# MCU.net
KiCad netlist of a schematic drawn in Altium Designer
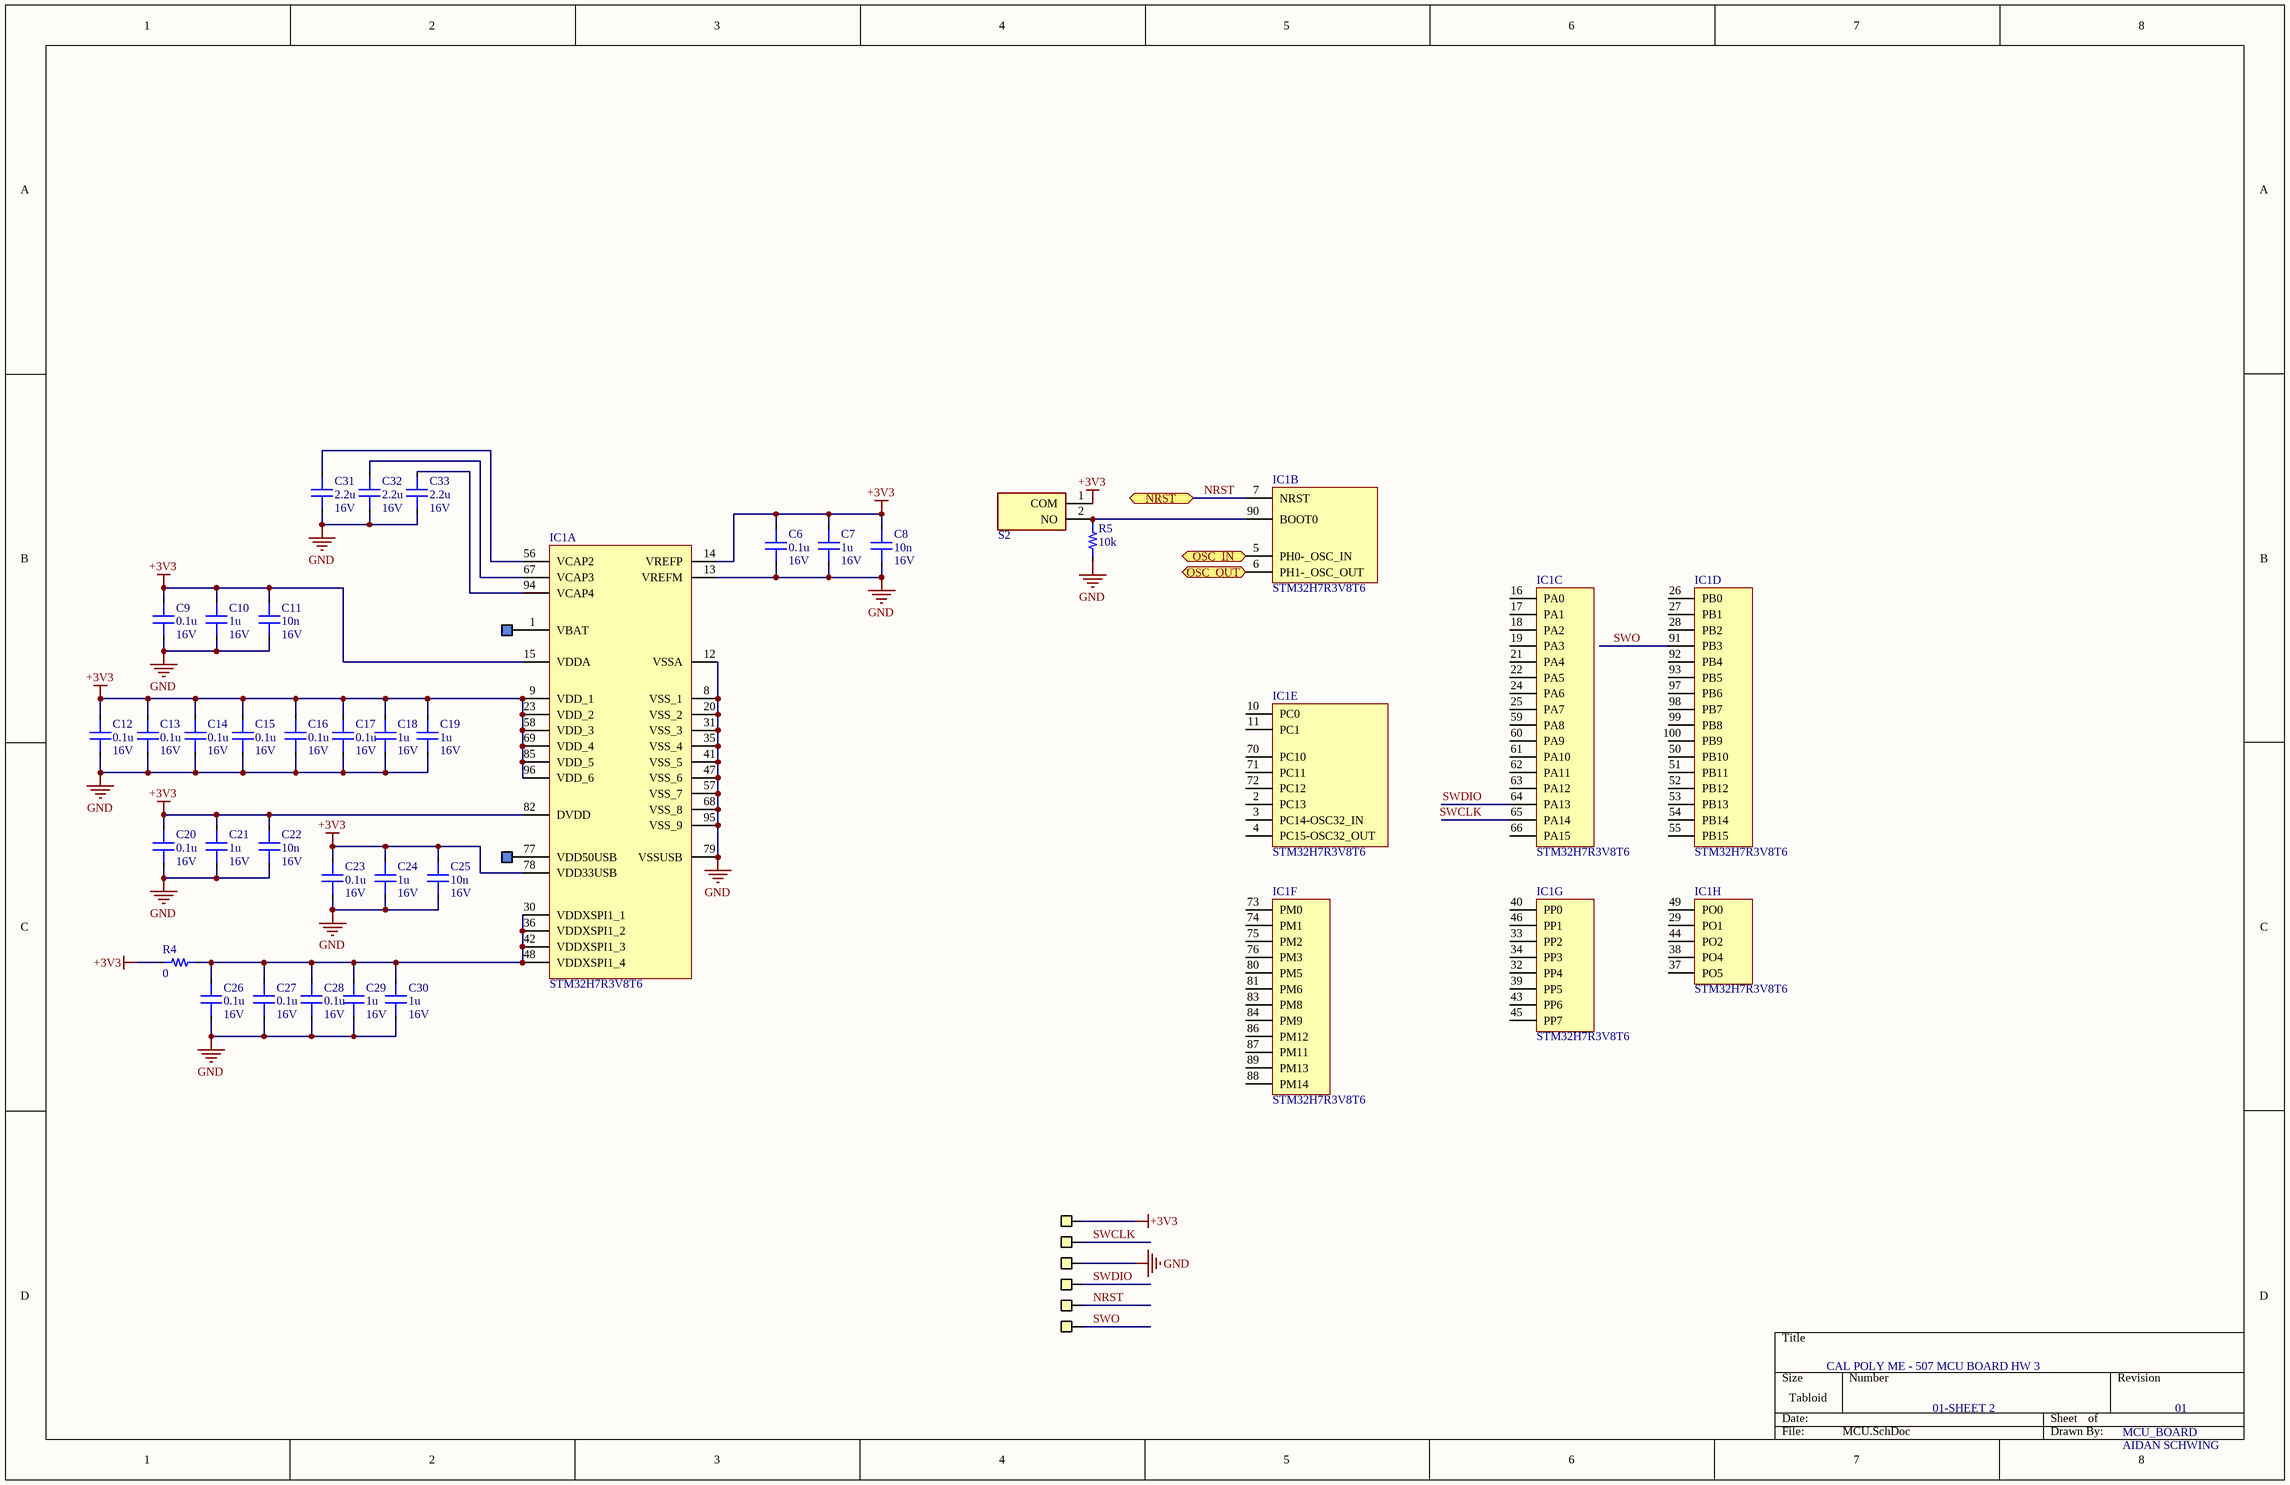
[diagram p0: MCU.SchDoc]

(export (version "E")
  (design (tool "Eeschema 10.0.6"))
  (components
    (comp (ref "C6")
      (value "0.1u")
      (footprint "0603_CAP")
      (fields (field (name "VOLTAGE") "16V") (field (name "Comment") "Capacitor"))
      (libsource (lib "Capacitors") (part "Capacitor"))
    )
    (comp (ref "C7")
      (value "1u")
      (footprint "0603_CAP")
      (fields (field (name "VOLTAGE") "16V") (field (name "Comment") "Capacitor"))
      (libsource (lib "Capacitors") (part "Capacitor"))
    )
    (comp (ref "C8")
      (value "10n")
      (footprint "0603_CAP")
      (fields (field (name "VOLTAGE") "16V") (field (name "Comment") "Capacitor"))
      (libsource (lib "Capacitors") (part "Capacitor"))
    )
    (comp (ref "C9")
      (value "0.1u")
      (footprint "0603_CAP")
      (fields (field (name "VOLTAGE") "16V") (field (name "Comment") "Capacitor"))
      (libsource (lib "Capacitors") (part "Capacitor"))
    )
    (comp (ref "C10")
      (value "1u")
      (footprint "0603_CAP")
      (fields (field (name "VOLTAGE") "16V") (field (name "Comment") "Capacitor"))
      (libsource (lib "Capacitors") (part "Capacitor"))
    )
    (comp (ref "C11")
      (value "10n")
      (footprint "0603_CAP")
      (fields (field (name "VOLTAGE") "16V") (field (name "Comment") "Capacitor"))
      (libsource (lib "Capacitors") (part "Capacitor"))
    )
    (comp (ref "C12")
      (value "0.1u")
      (footprint "0603_CAP")
      (fields (field (name "VOLTAGE") "16V") (field (name "Comment") "Capacitor"))
      (libsource (lib "Capacitors") (part "Capacitor"))
    )
    (comp (ref "C13")
      (value "0.1u")
      (footprint "0603_CAP")
      (fields (field (name "VOLTAGE") "16V") (field (name "Comment") "Capacitor"))
      (libsource (lib "Capacitors") (part "Capacitor"))
    )
    (comp (ref "C14")
      (value "0.1u")
      (footprint "0603_CAP")
      (fields (field (name "VOLTAGE") "16V") (field (name "Comment") "Capacitor"))
      (libsource (lib "Capacitors") (part "Capacitor"))
    )
    (comp (ref "C15")
      (value "0.1u")
      (footprint "0603_CAP")
      (fields (field (name "VOLTAGE") "16V") (field (name "Comment") "Capacitor"))
      (libsource (lib "Capacitors") (part "Capacitor"))
    )
    (comp (ref "C16")
      (value "0.1u")
      (footprint "0603_CAP")
      (fields (field (name "VOLTAGE") "16V") (field (name "Comment") "Capacitor"))
      (libsource (lib "Capacitors") (part "Capacitor"))
    )
    (comp (ref "C17")
      (value "0.1u")
      (footprint "0603_CAP")
      (fields (field (name "VOLTAGE") "16V") (field (name "Comment") "Capacitor"))
      (libsource (lib "Capacitors") (part "Capacitor"))
    )
    (comp (ref "C18")
      (value "1u")
      (footprint "0603_CAP")
      (fields (field (name "VOLTAGE") "16V") (field (name "Comment") "Capacitor"))
      (libsource (lib "Capacitors") (part "Capacitor"))
    )
    (comp (ref "C19")
      (value "1u")
      (footprint "0603_CAP")
      (fields (field (name "VOLTAGE") "16V") (field (name "Comment") "Capacitor"))
      (libsource (lib "Capacitors") (part "Capacitor"))
    )
    (comp (ref "C20")
      (value "0.1u")
      (footprint "0603_CAP")
      (fields (field (name "VOLTAGE") "16V") (field (name "Comment") "Capacitor"))
      (libsource (lib "Capacitors") (part "Capacitor"))
    )
    (comp (ref "C21")
      (value "1u")
      (footprint "0603_CAP")
      (fields (field (name "VOLTAGE") "16V") (field (name "Comment") "Capacitor"))
      (libsource (lib "Capacitors") (part "Capacitor"))
    )
    (comp (ref "C22")
      (value "10n")
      (footprint "0603_CAP")
      (fields (field (name "VOLTAGE") "16V") (field (name "Comment") "Capacitor"))
      (libsource (lib "Capacitors") (part "Capacitor"))
    )
    (comp (ref "C23")
      (value "0.1u")
      (footprint "0603_CAP")
      (fields (field (name "VOLTAGE") "16V") (field (name "Comment") "Capacitor"))
      (libsource (lib "Capacitors") (part "Capacitor"))
    )
    (comp (ref "C24")
      (value "1u")
      (footprint "0603_CAP")
      (fields (field (name "VOLTAGE") "16V") (field (name "Comment") "Capacitor"))
      (libsource (lib "Capacitors") (part "Capacitor"))
    )
    (comp (ref "C25")
      (value "10n")
      (footprint "0603_CAP")
      (fields (field (name "VOLTAGE") "16V") (field (name "Comment") "Capacitor"))
      (libsource (lib "Capacitors") (part "Capacitor"))
    )
    (comp (ref "C26")
      (value "0.1u")
      (footprint "0603_CAP")
      (fields (field (name "VOLTAGE") "16V") (field (name "Comment") "Capacitor"))
      (libsource (lib "Capacitors") (part "Capacitor"))
    )
    (comp (ref "C27")
      (value "0.1u")
      (footprint "0603_CAP")
      (fields (field (name "VOLTAGE") "16V") (field (name "Comment") "Capacitor"))
      (libsource (lib "Capacitors") (part "Capacitor"))
    )
    (comp (ref "C28")
      (value "0.1u")
      (footprint "0603_CAP")
      (fields (field (name "VOLTAGE") "16V") (field (name "Comment") "Capacitor"))
      (libsource (lib "Capacitors") (part "Capacitor"))
    )
    (comp (ref "C29")
      (value "1u")
      (footprint "0603_CAP")
      (fields (field (name "VOLTAGE") "16V") (field (name "Comment") "Capacitor"))
      (libsource (lib "Capacitors") (part "Capacitor"))
    )
    (comp (ref "C30")
      (value "1u")
      (footprint "0603_CAP")
      (fields (field (name "VOLTAGE") "16V") (field (name "Comment") "Capacitor"))
      (libsource (lib "Capacitors") (part "Capacitor"))
    )
    (comp (ref "C31")
      (value "2.2u")
      (footprint "0603_CAP")
      (fields (field (name "VOLTAGE") "16V") (field (name "Comment") "Capacitor"))
      (libsource (lib "Capacitors") (part "Capacitor"))
    )
    (comp (ref "C32")
      (value "2.2u")
      (footprint "0603_CAP")
      (fields (field (name "VOLTAGE") "16V") (field (name "Comment") "Capacitor"))
      (libsource (lib "Capacitors") (part "Capacitor"))
    )
    (comp (ref "C33")
      (value "2.2u")
      (footprint "0603_CAP")
      (fields (field (name "VOLTAGE") "16V") (field (name "Comment") "Capacitor"))
      (libsource (lib "Capacitors") (part "Capacitor"))
    )
    (comp (ref "IC1")
      (value "STM32H7R3V8T6")
      (footprint "Footprints:QFP50P1600X1600X160-100N")
      (description "IC MCU 32BIT 64KB FLASH 100LQFP")
      (libsource (lib "Microcontrollers") (part "STM32H7R3V8T6"))
    )
    (comp (ref "R4")
      (value "0")
      (footprint "0805_RES")
      (fields (field (name "Comment") "Resistor"))
      (libsource (lib "Resistors") (part "Resistor"))
    )
    (comp (ref "R5")
      (value "10k")
      (footprint "0603_RES")
      (fields (field (name "Comment") "Resistor"))
      (libsource (lib "Resistors") (part "Resistor"))
    )
    (comp (ref "S2")
      (value "DS04-254-2-01BK-SMT-TR")
      (footprint "DS04254201BKSMTTR")
      (fields (field (name "MOUSER PART NUMBER") "490-DS04254201BK-STR"))
      (libsource (lib "ElectroMechanical") (part "DS04-254-2-01BK-SMT-TR"))
    )
    (comp (ref "X2")
      (value "HeaderPad")
      (footprint "HeaderPad")
      (description "Pad for pin header")
      (libsource (lib "Connectors") (part "HeaderPad"))
    )
    (comp (ref "X3")
      (value "HeaderPad")
      (footprint "HeaderPad")
      (description "Pad for pin header")
      (libsource (lib "Connectors") (part "HeaderPad"))
    )
    (comp (ref "X4")
      (value "GenericPinHeader(0.1in)")
      (footprint "GenericPinHeader(.1in)")
      (description "Generic .1in(2.54mm) pitch pin header")
      (libsource (lib "Connectors") (part "GenericPinHeader(0.1in)"))
    )
    (comp (ref "X5")
      (value "GenericPinHeader(0.1in)")
      (footprint "GenericPinHeader(.1in)")
      (description "Generic .1in(2.54mm) pitch pin header")
      (libsource (lib "Connectors") (part "GenericPinHeader(0.1in)"))
    )
    (comp (ref "X6")
      (value "GenericPinHeader(0.1in)")
      (footprint "GenericPinHeader(.1in)")
      (description "Generic .1in(2.54mm) pitch pin header")
      (libsource (lib "Connectors") (part "GenericPinHeader(0.1in)"))
    )
    (comp (ref "X7")
      (value "GenericPinHeader(0.1in)")
      (footprint "GenericPinHeader(.1in)")
      (description "Generic .1in(2.54mm) pitch pin header")
      (libsource (lib "Connectors") (part "GenericPinHeader(0.1in)"))
    )
    (comp (ref "X8")
      (value "GenericPinHeader(0.1in)")
      (footprint "GenericPinHeader(.1in)")
      (description "Generic .1in(2.54mm) pitch pin header")
      (libsource (lib "Connectors") (part "GenericPinHeader(0.1in)"))
    )
    (comp (ref "X9")
      (value "GenericPinHeader(0.1in)")
      (footprint "GenericPinHeader(.1in)")
      (description "Generic .1in(2.54mm) pitch pin header")
      (libsource (lib "Connectors") (part "GenericPinHeader(0.1in)"))
    )
  )
  (nets
    (net (code "1") (name "+3V3") (class "Default")
      (node (ref "C10") (pin "2") (pinfunction "2_2") (pintype "passive"))
      (node (ref "C11") (pin "2") (pinfunction "2_2") (pintype "passive"))
      (node (ref "C12") (pin "2") (pinfunction "2_2") (pintype "passive"))
      (node (ref "C13") (pin "2") (pinfunction "2_2") (pintype "passive"))
      (node (ref "C14") (pin "2") (pinfunction "2_2") (pintype "passive"))
      (node (ref "C15") (pin "2") (pinfunction "2_2") (pintype "passive"))
      (node (ref "C16") (pin "2") (pinfunction "2_2") (pintype "passive"))
      (node (ref "C17") (pin "2") (pinfunction "2_2") (pintype "passive"))
      (node (ref "C18") (pin "2") (pinfunction "2_2") (pintype "passive"))
      (node (ref "C19") (pin "2") (pinfunction "2_2") (pintype "passive"))
      (node (ref "C20") (pin "2") (pinfunction "2_2") (pintype "passive"))
      (node (ref "C21") (pin "2") (pinfunction "2_2") (pintype "passive"))
      (node (ref "C22") (pin "2") (pinfunction "2_2") (pintype "passive"))
      (node (ref "C23") (pin "2") (pinfunction "2_2") (pintype "passive"))
      (node (ref "C24") (pin "2") (pinfunction "2_2") (pintype "passive"))
      (node (ref "C25") (pin "2") (pinfunction "2_2") (pintype "passive"))
      (node (ref "C6") (pin "2") (pinfunction "2_2") (pintype "passive"))
      (node (ref "C7") (pin "2") (pinfunction "2_2") (pintype "passive"))
      (node (ref "C8") (pin "2") (pinfunction "2_2") (pintype "passive"))
      (node (ref "C9") (pin "2") (pinfunction "2_2") (pintype "passive"))
      (node (ref "IC1") (pin "14") (pinfunction "VREFP_14") (pintype "passive"))
      (node (ref "IC1") (pin "15") (pinfunction "VDDA_15") (pintype "passive"))
      (node (ref "IC1") (pin "23") (pinfunction "VDD_2_23") (pintype "passive"))
      (node (ref "IC1") (pin "58") (pinfunction "VDD_3_58") (pintype "passive"))
      (node (ref "IC1") (pin "69") (pinfunction "VDD_4_69") (pintype "passive"))
      (node (ref "IC1") (pin "78") (pinfunction "VDD33USB_78") (pintype "passive"))
      (node (ref "IC1") (pin "82") (pinfunction "DVDD_82") (pintype "passive"))
      (node (ref "IC1") (pin "85") (pinfunction "VDD_5_85") (pintype "passive"))
      (node (ref "IC1") (pin "9") (pinfunction "VDD_1_9") (pintype "passive"))
      (node (ref "IC1") (pin "96") (pinfunction "VDD_6_96") (pintype "passive"))
      (node (ref "R4") (pin "1") (pinfunction "1_1") (pintype "passive"))
      (node (ref "S2") (pin "1") (pinfunction "COM_1") (pintype "passive"))
      (node (ref "X4") (pin "1") (pinfunction "Pin_1") (pintype "passive"))
    )
    (net (code "2") (name "/NRST") (class "Default")
      (node (ref "IC1") (pin "7") (pinfunction "NRST_7") (pintype "passive"))
      (node (ref "X8") (pin "1") (pinfunction "Pin_1") (pintype "passive"))
    )
    (net (code "3") (name "/OSC_IN") (class "Default")
      (node (ref "IC1") (pin "5") (pinfunction "PH0-_OSC_IN_5") (pintype "passive"))
    )
    (net (code "4") (name "/OSC_OUT") (class "Default")
      (node (ref "IC1") (pin "6") (pinfunction "PH1-_OSC_OUT_6") (pintype "passive"))
    )
    (net (code "5") (name "/SWCLK") (class "Default")
      (node (ref "IC1") (pin "65") (pinfunction "PA14_65") (pintype "passive"))
      (node (ref "X5") (pin "1") (pinfunction "Pin_1") (pintype "passive"))
    )
    (net (code "6") (name "/SWDIO") (class "Default")
      (node (ref "IC1") (pin "64") (pinfunction "PA13_64") (pintype "passive"))
      (node (ref "X7") (pin "1") (pinfunction "Pin_1") (pintype "passive"))
    )
    (net (code "7") (name "/SWO") (class "Default")
      (node (ref "IC1") (pin "91") (pinfunction "PB3_91") (pintype "passive"))
      (node (ref "X9") (pin "1") (pinfunction "Pin_1") (pintype "passive"))
    )
    (net (code "8") (name "GND") (class "Default")
      (node (ref "C10") (pin "1") (pinfunction "1_1") (pintype "passive"))
      (node (ref "C11") (pin "1") (pinfunction "1_1") (pintype "passive"))
      (node (ref "C12") (pin "1") (pinfunction "1_1") (pintype "passive"))
      (node (ref "C13") (pin "1") (pinfunction "1_1") (pintype "passive"))
      (node (ref "C14") (pin "1") (pinfunction "1_1") (pintype "passive"))
      (node (ref "C15") (pin "1") (pinfunction "1_1") (pintype "passive"))
      (node (ref "C16") (pin "1") (pinfunction "1_1") (pintype "passive"))
      (node (ref "C17") (pin "1") (pinfunction "1_1") (pintype "passive"))
      (node (ref "C18") (pin "1") (pinfunction "1_1") (pintype "passive"))
      (node (ref "C19") (pin "1") (pinfunction "1_1") (pintype "passive"))
      (node (ref "C20") (pin "1") (pinfunction "1_1") (pintype "passive"))
      (node (ref "C21") (pin "1") (pinfunction "1_1") (pintype "passive"))
      (node (ref "C22") (pin "1") (pinfunction "1_1") (pintype "passive"))
      (node (ref "C23") (pin "1") (pinfunction "1_1") (pintype "passive"))
      (node (ref "C24") (pin "1") (pinfunction "1_1") (pintype "passive"))
      (node (ref "C25") (pin "1") (pinfunction "1_1") (pintype "passive"))
      (node (ref "C26") (pin "1") (pinfunction "1_1") (pintype "passive"))
      (node (ref "C27") (pin "1") (pinfunction "1_1") (pintype "passive"))
      (node (ref "C28") (pin "1") (pinfunction "1_1") (pintype "passive"))
      (node (ref "C29") (pin "1") (pinfunction "1_1") (pintype "passive"))
      (node (ref "C30") (pin "1") (pinfunction "1_1") (pintype "passive"))
      (node (ref "C31") (pin "1") (pinfunction "1_1") (pintype "passive"))
      (node (ref "C32") (pin "1") (pinfunction "1_1") (pintype "passive"))
      (node (ref "C33") (pin "1") (pinfunction "1_1") (pintype "passive"))
      (node (ref "C6") (pin "1") (pinfunction "1_1") (pintype "passive"))
      (node (ref "C7") (pin "1") (pinfunction "1_1") (pintype "passive"))
      (node (ref "C8") (pin "1") (pinfunction "1_1") (pintype "passive"))
      (node (ref "C9") (pin "1") (pinfunction "1_1") (pintype "passive"))
      (node (ref "IC1") (pin "12") (pinfunction "VSSA_12") (pintype "passive"))
      (node (ref "IC1") (pin "13") (pinfunction "VREFM_13") (pintype "passive"))
      (node (ref "IC1") (pin "20") (pinfunction "VSS_2_20") (pintype "passive"))
      (node (ref "IC1") (pin "31") (pinfunction "VSS_3_31") (pintype "passive"))
      (node (ref "IC1") (pin "35") (pinfunction "VSS_4_35") (pintype "passive"))
      (node (ref "IC1") (pin "41") (pinfunction "VSS_5_41") (pintype "passive"))
      (node (ref "IC1") (pin "47") (pinfunction "VSS_6_47") (pintype "passive"))
      (node (ref "IC1") (pin "57") (pinfunction "VSS_7_57") (pintype "passive"))
      (node (ref "IC1") (pin "68") (pinfunction "VSS_8_68") (pintype "passive"))
      (node (ref "IC1") (pin "79") (pinfunction "VSSUSB_79") (pintype "passive"))
      (node (ref "IC1") (pin "8") (pinfunction "VSS_1_8") (pintype "passive"))
      (node (ref "IC1") (pin "95") (pinfunction "VSS_9_95") (pintype "passive"))
      (node (ref "R5") (pin "1") (pinfunction "1_1") (pintype "passive"))
      (node (ref "X6") (pin "1") (pinfunction "Pin_1") (pintype "passive"))
    )
    (net (code "9") (name "Net-(IC1A-VBAT)") (class "Default")
      (node (ref "IC1") (pin "1") (pinfunction "VBAT_1") (pintype "passive"))
      (node (ref "X2") (pin "1") (pinfunction "Pin_1") (pintype "passive"))
    )
    (net (code "10") (name "Net-(IC1A-VCAP2)") (class "Default")
      (node (ref "C31") (pin "2") (pinfunction "2_2") (pintype "passive"))
      (node (ref "IC1") (pin "56") (pinfunction "VCAP2_56") (pintype "passive"))
    )
    (net (code "11") (name "Net-(IC1A-VCAP3)") (class "Default")
      (node (ref "C32") (pin "2") (pinfunction "2_2") (pintype "passive"))
      (node (ref "IC1") (pin "67") (pinfunction "VCAP3_67") (pintype "passive"))
    )
    (net (code "12") (name "Net-(IC1A-VCAP4)") (class "Default")
      (node (ref "C33") (pin "2") (pinfunction "2_2") (pintype "passive"))
      (node (ref "IC1") (pin "94") (pinfunction "VCAP4_94") (pintype "passive"))
    )
    (net (code "13") (name "Net-(IC1A-VDD50USB)") (class "Default")
      (node (ref "IC1") (pin "77") (pinfunction "VDD50USB_77") (pintype "passive"))
      (node (ref "X3") (pin "1") (pinfunction "Pin_1") (pintype "passive"))
    )
    (net (code "14") (name "Net-(IC1A-VDDXSPI1_1)") (class "Default")
      (node (ref "C26") (pin "2") (pinfunction "2_2") (pintype "passive"))
      (node (ref "C27") (pin "2") (pinfunction "2_2") (pintype "passive"))
      (node (ref "C28") (pin "2") (pinfunction "2_2") (pintype "passive"))
      (node (ref "C29") (pin "2") (pinfunction "2_2") (pintype "passive"))
      (node (ref "C30") (pin "2") (pinfunction "2_2") (pintype "passive"))
      (node (ref "IC1") (pin "30") (pinfunction "VDDXSPI1_1_30") (pintype "passive"))
      (node (ref "IC1") (pin "36") (pinfunction "VDDXSPI1_2_36") (pintype "passive"))
      (node (ref "IC1") (pin "42") (pinfunction "VDDXSPI1_3_42") (pintype "passive"))
      (node (ref "IC1") (pin "48") (pinfunction "VDDXSPI1_4_48") (pintype "passive"))
      (node (ref "R4") (pin "2") (pinfunction "2_2") (pintype "passive"))
    )
    (net (code "15") (name "Net-(IC1B-BOOT0)") (class "Default")
      (node (ref "IC1") (pin "90") (pinfunction "BOOT0_90") (pintype "passive"))
      (node (ref "R5") (pin "2") (pinfunction "2_2") (pintype "passive"))
      (node (ref "S2") (pin "2") (pinfunction "NO_2") (pintype "passive"))
    )
    (net (code "16") (name "unconnected-(IC1C-PA0-Pad16)") (class "Default")
      (node (ref "IC1") (pin "16") (pinfunction "PA0_16") (pintype "passive"))
    )
    (net (code "17") (name "unconnected-(IC1C-PA1-Pad17)") (class "Default")
      (node (ref "IC1") (pin "17") (pinfunction "PA1_17") (pintype "passive"))
    )
    (net (code "18") (name "unconnected-(IC1C-PA2-Pad18)") (class "Default")
      (node (ref "IC1") (pin "18") (pinfunction "PA2_18") (pintype "passive"))
    )
    (net (code "19") (name "unconnected-(IC1C-PA3-Pad19)") (class "Default")
      (node (ref "IC1") (pin "19") (pinfunction "PA3_19") (pintype "passive"))
    )
    (net (code "20") (name "unconnected-(IC1C-PA4-Pad21)") (class "Default")
      (node (ref "IC1") (pin "21") (pinfunction "PA4_21") (pintype "passive"))
    )
    (net (code "21") (name "unconnected-(IC1C-PA5-Pad22)") (class "Default")
      (node (ref "IC1") (pin "22") (pinfunction "PA5_22") (pintype "passive"))
    )
    (net (code "22") (name "unconnected-(IC1C-PA6-Pad24)") (class "Default")
      (node (ref "IC1") (pin "24") (pinfunction "PA6_24") (pintype "passive"))
    )
    (net (code "23") (name "unconnected-(IC1C-PA7-Pad25)") (class "Default")
      (node (ref "IC1") (pin "25") (pinfunction "PA7_25") (pintype "passive"))
    )
    (net (code "24") (name "unconnected-(IC1C-PA8-Pad59)") (class "Default")
      (node (ref "IC1") (pin "59") (pinfunction "PA8_59") (pintype "passive"))
    )
    (net (code "25") (name "unconnected-(IC1C-PA9-Pad60)") (class "Default")
      (node (ref "IC1") (pin "60") (pinfunction "PA9_60") (pintype "passive"))
    )
    (net (code "26") (name "unconnected-(IC1C-PA10-Pad61)") (class "Default")
      (node (ref "IC1") (pin "61") (pinfunction "PA10_61") (pintype "passive"))
    )
    (net (code "27") (name "unconnected-(IC1C-PA11-Pad62)") (class "Default")
      (node (ref "IC1") (pin "62") (pinfunction "PA11_62") (pintype "passive"))
    )
    (net (code "28") (name "unconnected-(IC1C-PA12-Pad63)") (class "Default")
      (node (ref "IC1") (pin "63") (pinfunction "PA12_63") (pintype "passive"))
    )
    (net (code "29") (name "unconnected-(IC1C-PA15-Pad66)") (class "Default")
      (node (ref "IC1") (pin "66") (pinfunction "PA15_66") (pintype "passive"))
    )
    (net (code "30") (name "unconnected-(IC1D-PB0-Pad26)") (class "Default")
      (node (ref "IC1") (pin "26") (pinfunction "PB0_26") (pintype "passive"))
    )
    (net (code "31") (name "unconnected-(IC1D-PB1-Pad27)") (class "Default")
      (node (ref "IC1") (pin "27") (pinfunction "PB1_27") (pintype "passive"))
    )
    (net (code "32") (name "unconnected-(IC1D-PB2-Pad28)") (class "Default")
      (node (ref "IC1") (pin "28") (pinfunction "PB2_28") (pintype "passive"))
    )
    (net (code "33") (name "unconnected-(IC1D-PB4-Pad92)") (class "Default")
      (node (ref "IC1") (pin "92") (pinfunction "PB4_92") (pintype "passive"))
    )
    (net (code "34") (name "unconnected-(IC1D-PB5-Pad93)") (class "Default")
      (node (ref "IC1") (pin "93") (pinfunction "PB5_93") (pintype "passive"))
    )
    (net (code "35") (name "unconnected-(IC1D-PB6-Pad97)") (class "Default")
      (node (ref "IC1") (pin "97") (pinfunction "PB6_97") (pintype "passive"))
    )
    (net (code "36") (name "unconnected-(IC1D-PB7-Pad98)") (class "Default")
      (node (ref "IC1") (pin "98") (pinfunction "PB7_98") (pintype "passive"))
    )
    (net (code "37") (name "unconnected-(IC1D-PB8-Pad99)") (class "Default")
      (node (ref "IC1") (pin "99") (pinfunction "PB8_99") (pintype "passive"))
    )
    (net (code "38") (name "unconnected-(IC1D-PB9-Pad100)") (class "Default")
      (node (ref "IC1") (pin "100") (pinfunction "PB9_100") (pintype "passive"))
    )
    (net (code "39") (name "unconnected-(IC1D-PB10-Pad50)") (class "Default")
      (node (ref "IC1") (pin "50") (pinfunction "PB10_50") (pintype "passive"))
    )
    (net (code "40") (name "unconnected-(IC1D-PB11-Pad51)") (class "Default")
      (node (ref "IC1") (pin "51") (pinfunction "PB11_51") (pintype "passive"))
    )
    (net (code "41") (name "unconnected-(IC1D-PB12-Pad52)") (class "Default")
      (node (ref "IC1") (pin "52") (pinfunction "PB12_52") (pintype "passive"))
    )
    (net (code "42") (name "unconnected-(IC1D-PB13-Pad53)") (class "Default")
      (node (ref "IC1") (pin "53") (pinfunction "PB13_53") (pintype "passive"))
    )
    (net (code "43") (name "unconnected-(IC1D-PB14-Pad54)") (class "Default")
      (node (ref "IC1") (pin "54") (pinfunction "PB14_54") (pintype "passive"))
    )
    (net (code "44") (name "unconnected-(IC1D-PB15-Pad55)") (class "Default")
      (node (ref "IC1") (pin "55") (pinfunction "PB15_55") (pintype "passive"))
    )
    (net (code "45") (name "unconnected-(IC1E-PC0-Pad10)") (class "Default")
      (node (ref "IC1") (pin "10") (pinfunction "PC0_10") (pintype "passive"))
    )
    (net (code "46") (name "unconnected-(IC1E-PC1-Pad11)") (class "Default")
      (node (ref "IC1") (pin "11") (pinfunction "PC1_11") (pintype "passive"))
    )
    (net (code "47") (name "unconnected-(IC1E-PC10-Pad70)") (class "Default")
      (node (ref "IC1") (pin "70") (pinfunction "PC10_70") (pintype "passive"))
    )
    (net (code "48") (name "unconnected-(IC1E-PC11-Pad71)") (class "Default")
      (node (ref "IC1") (pin "71") (pinfunction "PC11_71") (pintype "passive"))
    )
    (net (code "49") (name "unconnected-(IC1E-PC12-Pad72)") (class "Default")
      (node (ref "IC1") (pin "72") (pinfunction "PC12_72") (pintype "passive"))
    )
    (net (code "50") (name "unconnected-(IC1E-PC13-Pad2)") (class "Default")
      (node (ref "IC1") (pin "2") (pinfunction "PC13_2") (pintype "passive"))
    )
    (net (code "51") (name "unconnected-(IC1E-PC14-OSC32_IN-Pad3)") (class "Default")
      (node (ref "IC1") (pin "3") (pinfunction "PC14-OSC32_IN_3") (pintype "passive"))
    )
    (net (code "52") (name "unconnected-(IC1E-PC15-OSC32_OUT-Pad4)") (class "Default")
      (node (ref "IC1") (pin "4") (pinfunction "PC15-OSC32_OUT_4") (pintype "passive"))
    )
    (net (code "53") (name "unconnected-(IC1F-PM0-Pad73)") (class "Default")
      (node (ref "IC1") (pin "73") (pinfunction "PM0_73") (pintype "passive"))
    )
    (net (code "54") (name "unconnected-(IC1F-PM1-Pad74)") (class "Default")
      (node (ref "IC1") (pin "74") (pinfunction "PM1_74") (pintype "passive"))
    )
    (net (code "55") (name "unconnected-(IC1F-PM2-Pad75)") (class "Default")
      (node (ref "IC1") (pin "75") (pinfunction "PM2_75") (pintype "passive"))
    )
    (net (code "56") (name "unconnected-(IC1F-PM3-Pad76)") (class "Default")
      (node (ref "IC1") (pin "76") (pinfunction "PM3_76") (pintype "passive"))
    )
    (net (code "57") (name "unconnected-(IC1F-PM5-Pad80)") (class "Default")
      (node (ref "IC1") (pin "80") (pinfunction "PM5_80") (pintype "passive"))
    )
    (net (code "58") (name "unconnected-(IC1F-PM6-Pad81)") (class "Default")
      (node (ref "IC1") (pin "81") (pinfunction "PM6_81") (pintype "passive"))
    )
    (net (code "59") (name "unconnected-(IC1F-PM8-Pad83)") (class "Default")
      (node (ref "IC1") (pin "83") (pinfunction "PM8_83") (pintype "passive"))
    )
    (net (code "60") (name "unconnected-(IC1F-PM9-Pad84)") (class "Default")
      (node (ref "IC1") (pin "84") (pinfunction "PM9_84") (pintype "passive"))
    )
    (net (code "61") (name "unconnected-(IC1F-PM11-Pad87)") (class "Default")
      (node (ref "IC1") (pin "87") (pinfunction "PM11_87") (pintype "passive"))
    )
    (net (code "62") (name "unconnected-(IC1F-PM12-Pad86)") (class "Default")
      (node (ref "IC1") (pin "86") (pinfunction "PM12_86") (pintype "passive"))
    )
    (net (code "63") (name "unconnected-(IC1F-PM13-Pad89)") (class "Default")
      (node (ref "IC1") (pin "89") (pinfunction "PM13_89") (pintype "passive"))
    )
    (net (code "64") (name "unconnected-(IC1F-PM14-Pad88)") (class "Default")
      (node (ref "IC1") (pin "88") (pinfunction "PM14_88") (pintype "passive"))
    )
    (net (code "65") (name "unconnected-(IC1G-PP0-Pad40)") (class "Default")
      (node (ref "IC1") (pin "40") (pinfunction "PP0_40") (pintype "passive"))
    )
    (net (code "66") (name "unconnected-(IC1G-PP1-Pad46)") (class "Default")
      (node (ref "IC1") (pin "46") (pinfunction "PP1_46") (pintype "passive"))
    )
    (net (code "67") (name "unconnected-(IC1G-PP2-Pad33)") (class "Default")
      (node (ref "IC1") (pin "33") (pinfunction "PP2_33") (pintype "passive"))
    )
    (net (code "68") (name "unconnected-(IC1G-PP3-Pad34)") (class "Default")
      (node (ref "IC1") (pin "34") (pinfunction "PP3_34") (pintype "passive"))
    )
    (net (code "69") (name "unconnected-(IC1G-PP4-Pad32)") (class "Default")
      (node (ref "IC1") (pin "32") (pinfunction "PP4_32") (pintype "passive"))
    )
    (net (code "70") (name "unconnected-(IC1G-PP5-Pad39)") (class "Default")
      (node (ref "IC1") (pin "39") (pinfunction "PP5_39") (pintype "passive"))
    )
    (net (code "71") (name "unconnected-(IC1G-PP6-Pad43)") (class "Default")
      (node (ref "IC1") (pin "43") (pinfunction "PP6_43") (pintype "passive"))
    )
    (net (code "72") (name "unconnected-(IC1G-PP7-Pad45)") (class "Default")
      (node (ref "IC1") (pin "45") (pinfunction "PP7_45") (pintype "passive"))
    )
    (net (code "73") (name "unconnected-(IC1H-PO0-Pad49)") (class "Default")
      (node (ref "IC1") (pin "49") (pinfunction "PO0_49") (pintype "passive"))
    )
    (net (code "74") (name "unconnected-(IC1H-PO1-Pad29)") (class "Default")
      (node (ref "IC1") (pin "29") (pinfunction "PO1_29") (pintype "passive"))
    )
    (net (code "75") (name "unconnected-(IC1H-PO2-Pad44)") (class "Default")
      (node (ref "IC1") (pin "44") (pinfunction "PO2_44") (pintype "passive"))
    )
    (net (code "76") (name "unconnected-(IC1H-PO4-Pad38)") (class "Default")
      (node (ref "IC1") (pin "38") (pinfunction "PO4_38") (pintype "passive"))
    )
    (net (code "77") (name "unconnected-(IC1H-PO5-Pad37)") (class "Default")
      (node (ref "IC1") (pin "37") (pinfunction "PO5_37") (pintype "passive"))
    )
  )
)
